# MCU.net
KiCad netlist of a schematic drawn in Altium Designer
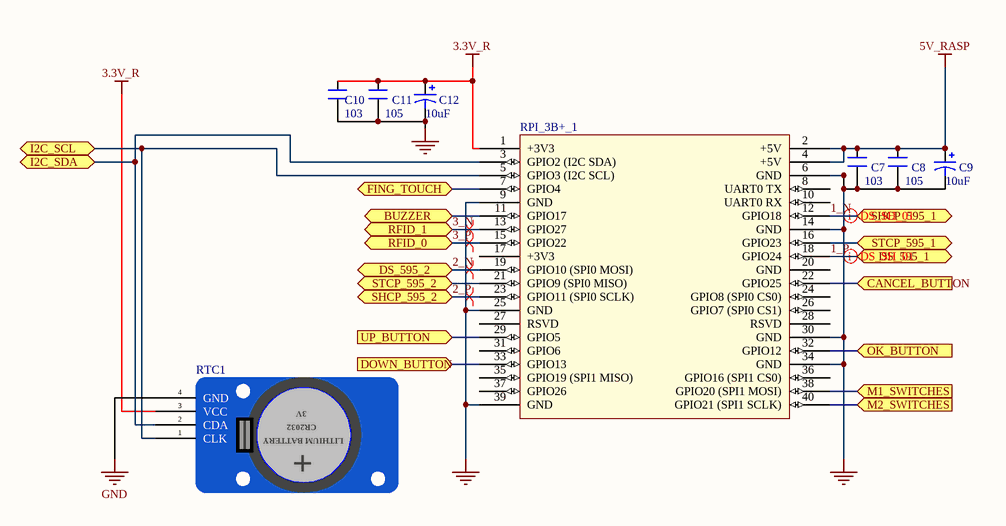
[diagram p0: MCU.SchDoc]

(export (version "E")
  (design (tool "Eeschema 10.0.6"))
  (components
    (comp (ref "C7")
      (value "103")
      (footprint "CN1")
      (description "Cap np  1pF - 472pF")
      (libsource (lib "syhaunguyen") (part "CN1"))
    )
    (comp (ref "C8")
      (value "105")
      (footprint "CN1")
      (description "Cap np  1pF - 472pF")
      (libsource (lib "syhaunguyen") (part "CN1"))
    )
    (comp (ref "C9")
      (value "10uF")
      (footprint "CP2/5")
      (description "Polarized Capacitor (Surface Mount)")
      (fields (field (name "PUBLISHER") "Altium Limited"))
      (libsource (lib "syhaunguyen") (part "Cap Pol3_1"))
    )
    (comp (ref "C10")
      (value "103")
      (footprint "CN1")
      (description "Cap np  1pF - 472pF")
      (libsource (lib "syhaunguyen") (part "CN1"))
    )
    (comp (ref "C11")
      (value "105")
      (footprint "CN1")
      (description "Cap np  1pF - 472pF")
      (libsource (lib "syhaunguyen") (part "CN1"))
    )
    (comp (ref "C12")
      (value "10uF")
      (footprint "CP2/5")
      (description "Polarized Capacitor (Surface Mount)")
      (fields (field (name "PUBLISHER") "Altium Limited"))
      (libsource (lib "syhaunguyen") (part "Cap Pol3_1"))
    )
    (comp (ref "RPI_3B+_1")
      (value "RPI GPIO Connector")
      (footprint "RPI-holes")
      (description "GPIO Header for Raspberry Pi A+/B+/Pi 2/Pi 3 - 2x20")
      (fields
        (field (name "MANUFACTURER") "SparkFun Electronics")
        (field (name "MANUFACTURER PART NUMBER") "PRT-14017")
      )
      (libsource (lib "rpi") (part "rpi connector_2holes"))
    )
    (comp (ref "RTC1")
      (value "6#RTC_DS3231_4Pin")
      (footprint "6#RTC_DS3231_4Pin")
      (libsource (lib "Sch") (part "6#RTC_DS3231_4Pin"))
    )
  )
  (nets
    (net (code "1") (name "/1_N") (class "Default")
      (node (ref "RPI_3B+_1") (pin "12") (pinfunction "GPIO18_12") (pintype "bidirectional"))
    )
    (net (code "2") (name "/1_P") (class "Default")
      (node (ref "RPI_3B+_1") (pin "18") (pinfunction "GPIO24_18") (pintype "bidirectional"))
    )
    (net (code "3") (name "/2_N") (class "Default")
      (node (ref "RPI_3B+_1") (pin "19") (pinfunction "GPIO10_(SPI0_MOSI)_19") (pintype "bidirectional"))
    )
    (net (code "4") (name "/2_P") (class "Default")
      (node (ref "RPI_3B+_1") (pin "23") (pinfunction "GPIO11_(SPI0_SCLK)_23") (pintype "bidirectional"))
    )
    (net (code "5") (name "/3_N") (class "Default")
      (node (ref "RPI_3B+_1") (pin "13") (pinfunction "GPIO27_13") (pintype "bidirectional"))
    )
    (net (code "6") (name "/3_P") (class "Default")
      (node (ref "RPI_3B+_1") (pin "15") (pinfunction "GPIO22_15") (pintype "bidirectional"))
    )
    (net (code "7") (name "/BUZZER") (class "Default")
      (node (ref "RPI_3B+_1") (pin "11") (pinfunction "GPIO17_11") (pintype "bidirectional"))
    )
    (net (code "8") (name "/CANCEL_BUTTON") (class "Default")
      (node (ref "RPI_3B+_1") (pin "22") (pinfunction "GPIO25_22") (pintype "bidirectional"))
    )
    (net (code "9") (name "/DOWN_BUTTON") (class "Default")
      (node (ref "RPI_3B+_1") (pin "33") (pinfunction "GPIO13_33") (pintype "bidirectional"))
    )
    (net (code "10") (name "/FING_TOUCH") (class "Default")
      (node (ref "RPI_3B+_1") (pin "7") (pinfunction "GPIO4_7") (pintype "bidirectional"))
    )
    (net (code "11") (name "/I2C_SCL") (class "Default")
      (node (ref "RPI_3B+_1") (pin "5") (pinfunction "GPIO3_(I2C_SCL)_5") (pintype "bidirectional"))
      (node (ref "RTC1") (pin "1") (pinfunction "CLK_1") (pintype "passive"))
    )
    (net (code "12") (name "/I2C_SDA") (class "Default")
      (node (ref "RPI_3B+_1") (pin "3") (pinfunction "GPIO2_(I2C_SDA)_3") (pintype "bidirectional"))
      (node (ref "RTC1") (pin "2") (pinfunction "CDA_2") (pintype "passive"))
    )
    (net (code "13") (name "/M1_SWITCHES") (class "Default")
      (node (ref "RPI_3B+_1") (pin "38") (pinfunction "GPIO20_(SPI1_MOSI)_38") (pintype "bidirectional"))
    )
    (net (code "14") (name "/M2_SWITCHES") (class "Default")
      (node (ref "RPI_3B+_1") (pin "40") (pinfunction "GPIO21_(SPI1_SCLK)_40") (pintype "bidirectional"))
    )
    (net (code "15") (name "/OK_BUTTON") (class "Default")
      (node (ref "RPI_3B+_1") (pin "32") (pinfunction "GPIO12_32") (pintype "bidirectional"))
    )
    (net (code "16") (name "/STCP_595_1") (class "Default")
      (node (ref "RPI_3B+_1") (pin "16") (pinfunction "GPIO23_16") (pintype "bidirectional"))
    )
    (net (code "17") (name "/STCP_595_2") (class "Default")
      (node (ref "RPI_3B+_1") (pin "21") (pinfunction "GPIO9_(SPI0_MISO)_21") (pintype "bidirectional"))
    )
    (net (code "18") (name "/UP_BUTTON") (class "Default")
      (node (ref "RPI_3B+_1") (pin "29") (pinfunction "GPIO5_29") (pintype "bidirectional"))
    )
    (net (code "19") (name "3.3V_R") (class "Default")
      (node (ref "C10") (pin "2") (pinfunction "2_2") (pintype "passive"))
      (node (ref "C11") (pin "2") (pinfunction "2_2") (pintype "passive"))
      (node (ref "C12") (pin "1") (pinfunction "1_1") (pintype "passive"))
      (node (ref "RPI_3B+_1") (pin "1") (pinfunction "+3V3_1") (pintype "power_in"))
      (node (ref "RTC1") (pin "3") (pinfunction "VCC_3") (pintype "passive"))
    )
    (net (code "20") (name "5V_RASP") (class "Default")
      (node (ref "C7") (pin "2") (pinfunction "2_2") (pintype "passive"))
      (node (ref "C8") (pin "2") (pinfunction "2_2") (pintype "passive"))
      (node (ref "C9") (pin "1") (pinfunction "1_1") (pintype "passive"))
      (node (ref "RPI_3B+_1") (pin "2") (pinfunction "+5V_2") (pintype "power_in"))
      (node (ref "RPI_3B+_1") (pin "4") (pinfunction "+5V_4") (pintype "power_in"))
    )
    (net (code "21") (name "GND") (class "Default")
      (node (ref "C10") (pin "1") (pinfunction "1_1") (pintype "passive"))
      (node (ref "C11") (pin "1") (pinfunction "1_1") (pintype "passive"))
      (node (ref "C12") (pin "2") (pinfunction "2_2") (pintype "passive"))
      (node (ref "C7") (pin "1") (pinfunction "1_1") (pintype "passive"))
      (node (ref "C8") (pin "1") (pinfunction "1_1") (pintype "passive"))
      (node (ref "C9") (pin "2") (pinfunction "2_2") (pintype "passive"))
      (node (ref "RPI_3B+_1") (pin "14") (pinfunction "GND_14") (pintype "power_in"))
      (node (ref "RPI_3B+_1") (pin "25") (pinfunction "GND_25") (pintype "power_in"))
      (node (ref "RPI_3B+_1") (pin "30") (pinfunction "GND_30") (pintype "power_in"))
      (node (ref "RPI_3B+_1") (pin "34") (pinfunction "GND_34") (pintype "passive"))
      (node (ref "RPI_3B+_1") (pin "39") (pinfunction "GND_39") (pintype "power_in"))
      (node (ref "RPI_3B+_1") (pin "6") (pinfunction "GND_6") (pintype "power_in"))
      (node (ref "RPI_3B+_1") (pin "9") (pinfunction "GND_9") (pintype "power_in"))
      (node (ref "RTC1") (pin "4") (pinfunction "GND_4") (pintype "passive"))
    )
    (net (code "22") (name "unconnected-(RPI_3B+_1-+3V3-Pad17)") (class "Default")
      (node (ref "RPI_3B+_1") (pin "17") (pinfunction "+3V3_17") (pintype "power_in"))
    )
    (net (code "23") (name "unconnected-(RPI_3B+_1-GND-Pad20)") (class "Default")
      (node (ref "RPI_3B+_1") (pin "20") (pinfunction "GND_20") (pintype "power_in"))
    )
    (net (code "24") (name "unconnected-(RPI_3B+_1-GPIO6-Pad31)") (class "Default")
      (node (ref "RPI_3B+_1") (pin "31") (pinfunction "GPIO6_31") (pintype "bidirectional"))
    )
    (net (code "25") (name "unconnected-(RPI_3B+_1-GPIO7_(SPI0_CS1)-Pad26)") (class "Default")
      (node (ref "RPI_3B+_1") (pin "26") (pinfunction "GPIO7_(SPI0_CS1)_26") (pintype "bidirectional"))
    )
    (net (code "26") (name "unconnected-(RPI_3B+_1-GPIO8_(SPI0_CS0)-Pad24)") (class "Default")
      (node (ref "RPI_3B+_1") (pin "24") (pinfunction "GPIO8_(SPI0_CS0)_24") (pintype "bidirectional"))
    )
    (net (code "27") (name "unconnected-(RPI_3B+_1-GPIO16_(SPI1_CS0)-Pad36)") (class "Default")
      (node (ref "RPI_3B+_1") (pin "36") (pinfunction "GPIO16_(SPI1_CS0)_36") (pintype "bidirectional"))
    )
    (net (code "28") (name "unconnected-(RPI_3B+_1-GPIO19_(SPI1_MISO)-Pad35)") (class "Default")
      (node (ref "RPI_3B+_1") (pin "35") (pinfunction "GPIO19_(SPI1_MISO)_35") (pintype "bidirectional"))
    )
    (net (code "29") (name "unconnected-(RPI_3B+_1-GPIO26-Pad37)") (class "Default")
      (node (ref "RPI_3B+_1") (pin "37") (pinfunction "GPIO26_37") (pintype "bidirectional"))
    )
    (net (code "30") (name "unconnected-(RPI_3B+_1-RSVD-Pad27)") (class "Default")
      (node (ref "RPI_3B+_1") (pin "27") (pinfunction "RSVD_27") (pintype "passive"))
    )
    (net (code "31") (name "unconnected-(RPI_3B+_1-RSVD-Pad28)") (class "Default")
      (node (ref "RPI_3B+_1") (pin "28") (pinfunction "RSVD_28") (pintype "passive"))
    )
    (net (code "32") (name "unconnected-(RPI_3B+_1-UART0_RX-Pad10)") (class "Default")
      (node (ref "RPI_3B+_1") (pin "10") (pinfunction "UART0_RX_10") (pintype "bidirectional"))
    )
    (net (code "33") (name "unconnected-(RPI_3B+_1-UART0_TX-Pad8)") (class "Default")
      (node (ref "RPI_3B+_1") (pin "8") (pinfunction "UART0_TX_8") (pintype "bidirectional"))
    )
  )
)
